# ADP-CI-V1.net
KiCad netlist of a schematic drawn in Altium Designer
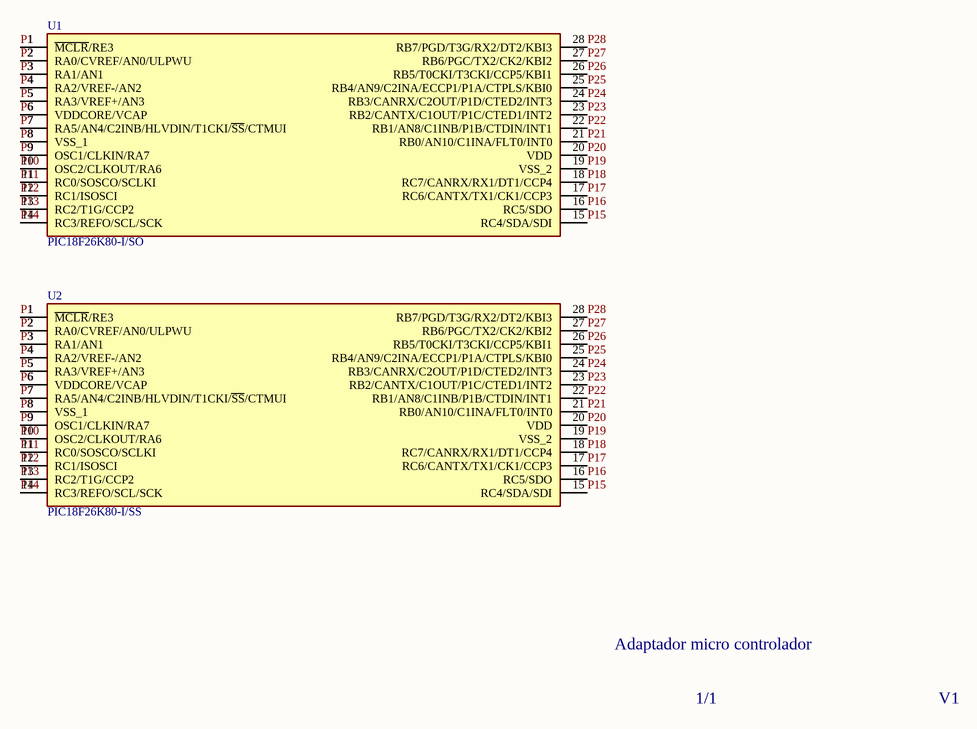
[diagram p0: ADP-CI-V1.SchDoc]

(export (version "E")
  (design (tool "Eeschema 10.0.6"))
  (components
    (comp (ref "U1")
      (value "PIC18F26K80-I/SO")
      (footprint "SOIC-28")
      (description "Microcontrolador")
      (fields (field (name "MOUSER PART NUMBER") "579-PIC18F26K80-I/SO"))
      (libsource (lib "Lib SMD") (part "PIC18F26K80-I/SO"))
    )
    (comp (ref "U2")
      (value "PIC18F26K80-I/SS")
      (footprint "SSOP-28")
      (description "Microcontrolador")
      (fields (field (name "MOUSER PART NUMBER") "579-PIC18F26K80-I/SS"))
      (libsource (lib "Lib SMD") (part "PIC18F26K80-I/SS"))
    )
  )
  (nets
    (net (code "1") (name "/P1") (class "Default")
      (node (ref "U1") (pin "1") (pinfunction "~{MCLR}/RE3_1") (pintype "passive"))
      (node (ref "U2") (pin "1") (pinfunction "~{MCLR}/RE3_1") (pintype "passive"))
    )
    (net (code "2") (name "/P2") (class "Default")
      (node (ref "U1") (pin "2") (pinfunction "RA0/CVREF/AN0/ULPWU_2") (pintype "passive"))
      (node (ref "U2") (pin "2") (pinfunction "RA0/CVREF/AN0/ULPWU_2") (pintype "passive"))
    )
    (net (code "3") (name "/P3") (class "Default")
      (node (ref "U1") (pin "3") (pinfunction "RA1/AN1_3") (pintype "passive"))
      (node (ref "U2") (pin "3") (pinfunction "RA1/AN1_3") (pintype "passive"))
    )
    (net (code "4") (name "/P4") (class "Default")
      (node (ref "U1") (pin "4") (pinfunction "RA2/VREF-/AN2_4") (pintype "passive"))
      (node (ref "U2") (pin "4") (pinfunction "RA2/VREF-/AN2_4") (pintype "passive"))
    )
    (net (code "5") (name "/P5") (class "Default")
      (node (ref "U1") (pin "5") (pinfunction "RA3/VREF+/AN3_5") (pintype "passive"))
      (node (ref "U2") (pin "5") (pinfunction "RA3/VREF+/AN3_5") (pintype "passive"))
    )
    (net (code "6") (name "/P6") (class "Default")
      (node (ref "U1") (pin "6") (pinfunction "VDDCORE/VCAP_6") (pintype "passive"))
      (node (ref "U2") (pin "6") (pinfunction "VDDCORE/VCAP_6") (pintype "passive"))
    )
    (net (code "7") (name "/P7") (class "Default")
      (node (ref "U1") (pin "7") (pinfunction "RA5/AN4/C2INB/HLVDIN/T1CKI/~{SS}/CTMUI_7") (pintype "passive"))
      (node (ref "U2") (pin "7") (pinfunction "RA5/AN4/C2INB/HLVDIN/T1CKI/~{SS}/CTMUI_7") (pintype "passive"))
    )
    (net (code "8") (name "/P8") (class "Default")
      (node (ref "U1") (pin "8") (pinfunction "VSS_1_8") (pintype "passive"))
      (node (ref "U2") (pin "8") (pinfunction "VSS_1_8") (pintype "passive"))
    )
    (net (code "9") (name "/P9") (class "Default")
      (node (ref "U1") (pin "9") (pinfunction "OSC1/CLKIN/RA7_9") (pintype "passive"))
      (node (ref "U2") (pin "9") (pinfunction "OSC1/CLKIN/RA7_9") (pintype "passive"))
    )
    (net (code "10") (name "/P10") (class "Default")
      (node (ref "U1") (pin "10") (pinfunction "OSC2/CLKOUT/RA6_10") (pintype "passive"))
      (node (ref "U2") (pin "10") (pinfunction "OSC2/CLKOUT/RA6_10") (pintype "passive"))
    )
    (net (code "11") (name "/P11") (class "Default")
      (node (ref "U1") (pin "11") (pinfunction "RC0/SOSCO/SCLKI_11") (pintype "passive"))
      (node (ref "U2") (pin "11") (pinfunction "RC0/SOSCO/SCLKI_11") (pintype "passive"))
    )
    (net (code "12") (name "/P12") (class "Default")
      (node (ref "U1") (pin "12") (pinfunction "RC1/ISOSCI_12") (pintype "passive"))
      (node (ref "U2") (pin "12") (pinfunction "RC1/ISOSCI_12") (pintype "passive"))
    )
    (net (code "13") (name "/P13") (class "Default")
      (node (ref "U1") (pin "13") (pinfunction "RC2/T1G/CCP2_13") (pintype "passive"))
      (node (ref "U2") (pin "13") (pinfunction "RC2/T1G/CCP2_13") (pintype "passive"))
    )
    (net (code "14") (name "/P14") (class "Default")
      (node (ref "U1") (pin "14") (pinfunction "RC3/REFO/SCL/SCK_14") (pintype "passive"))
      (node (ref "U2") (pin "14") (pinfunction "RC3/REFO/SCL/SCK_14") (pintype "passive"))
    )
    (net (code "15") (name "/P15") (class "Default")
      (node (ref "U1") (pin "15") (pinfunction "RC4/SDA/SDI_15") (pintype "passive"))
      (node (ref "U2") (pin "15") (pinfunction "RC4/SDA/SDI_15") (pintype "passive"))
    )
    (net (code "16") (name "/P16") (class "Default")
      (node (ref "U1") (pin "16") (pinfunction "RC5/SDO_16") (pintype "passive"))
      (node (ref "U2") (pin "16") (pinfunction "RC5/SDO_16") (pintype "passive"))
    )
    (net (code "17") (name "/P17") (class "Default")
      (node (ref "U1") (pin "17") (pinfunction "RC6/CANTX/TX1/CK1/CCP3_17") (pintype "passive"))
      (node (ref "U2") (pin "17") (pinfunction "RC6/CANTX/TX1/CK1/CCP3_17") (pintype "passive"))
    )
    (net (code "18") (name "/P18") (class "Default")
      (node (ref "U1") (pin "18") (pinfunction "RC7/CANRX/RX1/DT1/CCP4_18") (pintype "passive"))
      (node (ref "U2") (pin "18") (pinfunction "RC7/CANRX/RX1/DT1/CCP4_18") (pintype "passive"))
    )
    (net (code "19") (name "/P19") (class "Default")
      (node (ref "U1") (pin "19") (pinfunction "VSS_2_19") (pintype "passive"))
      (node (ref "U2") (pin "19") (pinfunction "VSS_2_19") (pintype "passive"))
    )
    (net (code "20") (name "/P20") (class "Default")
      (node (ref "U1") (pin "20") (pinfunction "VDD_20") (pintype "passive"))
      (node (ref "U2") (pin "20") (pinfunction "VDD_20") (pintype "passive"))
    )
    (net (code "21") (name "/P21") (class "Default")
      (node (ref "U1") (pin "21") (pinfunction "RB0/AN10/C1INA/FLT0/INT0_21") (pintype "passive"))
      (node (ref "U2") (pin "21") (pinfunction "RB0/AN10/C1INA/FLT0/INT0_21") (pintype "passive"))
    )
    (net (code "22") (name "/P22") (class "Default")
      (node (ref "U1") (pin "22") (pinfunction "RB1/AN8/C1INB/P1B/CTDIN/INT1_22") (pintype "passive"))
      (node (ref "U2") (pin "22") (pinfunction "RB1/AN8/C1INB/P1B/CTDIN/INT1_22") (pintype "passive"))
    )
    (net (code "23") (name "/P23") (class "Default")
      (node (ref "U1") (pin "23") (pinfunction "RB2/CANTX/C1OUT/P1C/CTED1/INT2_23") (pintype "passive"))
      (node (ref "U2") (pin "23") (pinfunction "RB2/CANTX/C1OUT/P1C/CTED1/INT2_23") (pintype "passive"))
    )
    (net (code "24") (name "/P24") (class "Default")
      (node (ref "U1") (pin "24") (pinfunction "RB3/CANRX/C2OUT/P1D/CTED2/INT3_24") (pintype "passive"))
      (node (ref "U2") (pin "24") (pinfunction "RB3/CANRX/C2OUT/P1D/CTED2/INT3_24") (pintype "passive"))
    )
    (net (code "25") (name "/P25") (class "Default")
      (node (ref "U1") (pin "25") (pinfunction "RB4/AN9/C2INA/ECCP1/P1A/CTPLS/KBI0_25") (pintype "passive"))
      (node (ref "U2") (pin "25") (pinfunction "RB4/AN9/C2INA/ECCP1/P1A/CTPLS/KBI0_25") (pintype "passive"))
    )
    (net (code "26") (name "/P26") (class "Default")
      (node (ref "U1") (pin "26") (pinfunction "RB5/T0CKI/T3CKI/CCP5/KBI1_26") (pintype "passive"))
      (node (ref "U2") (pin "26") (pinfunction "RB5/T0CKI/T3CKI/CCP5/KBI1_26") (pintype "passive"))
    )
    (net (code "27") (name "/P27") (class "Default")
      (node (ref "U1") (pin "27") (pinfunction "RB6/PGC/TX2/CK2/KBI2_27") (pintype "passive"))
      (node (ref "U2") (pin "27") (pinfunction "RB6/PGC/TX2/CK2/KBI2_27") (pintype "passive"))
    )
    (net (code "28") (name "/P28") (class "Default")
      (node (ref "U1") (pin "28") (pinfunction "RB7/PGD/T3G/RX2/DT2/KBI3_28") (pintype "passive"))
      (node (ref "U2") (pin "28") (pinfunction "RB7/PGD/T3G/RX2/DT2/KBI3_28") (pintype "passive"))
    )
  )
)
